# supply_switch.net
KiCad netlist of a schematic drawn in EAGLE
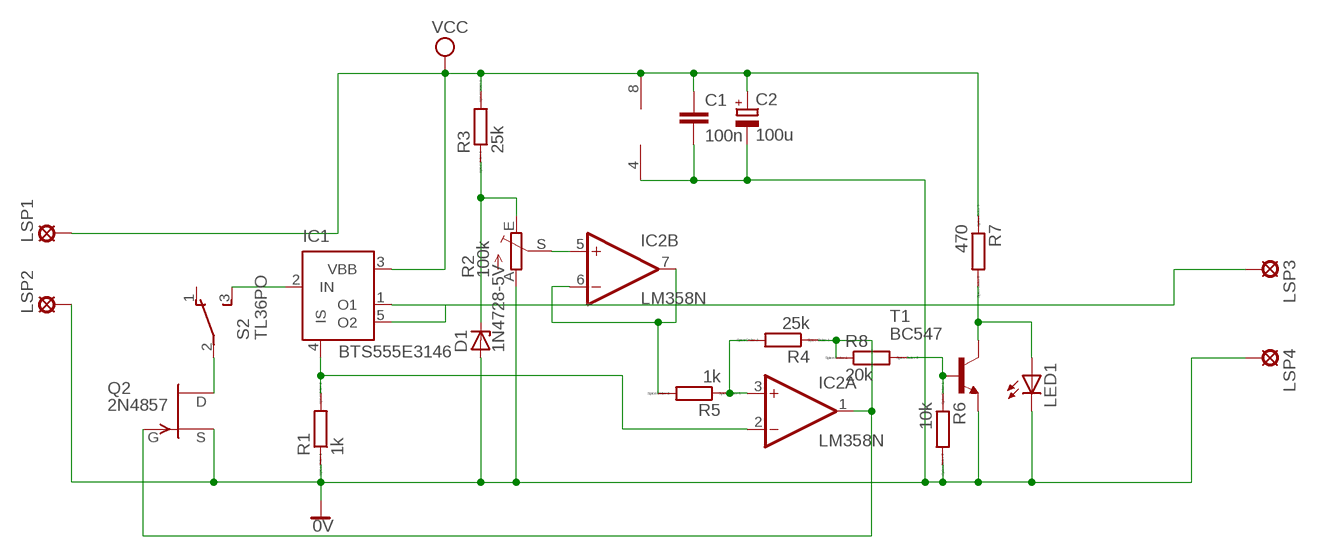
[diagram p0: schematic, sheet 1]

(export (version "E")
  (design (tool "Eeschema 10.0.6"))
  (components
    (comp (ref "C1")
      (value "100n")
      (footprint "eagle-import:C025-030X050")
      (libsource (lib "eagle-import") (part "C-EU025-030X050"))
    )
    (comp (ref "C2")
      (value "100u")
      (footprint "eagle-import:E3,5-10")
      (libsource (lib "eagle-import") (part "CPOL-EUE3.5-10"))
    )
    (comp (ref "D1")
      (value "1N4728-5V")
      (footprint "eagle-import:DO41Z10")
      (libsource (lib "eagle-import") (part "1N4728"))
    )
    (comp (ref "IC1")
      (value "BTS555E3146")
      (footprint "eagle-import:TO220-52")
      (libsource (lib "eagle-import") (part "BTS555E3146"))
    )
    (comp (ref "IC2")
      (value "LM358N")
      (footprint "eagle-import:DIL08")
      (libsource (lib "eagle-import") (part "LM358N"))
    )
    (comp (ref "LED1")
      (value "LED5MM")
      (footprint "eagle-import:LED5MM")
      (libsource (lib "eagle-import") (part "LED5MM"))
    )
    (comp (ref "LSP1")
      (value "SE14")
      (footprint "eagle-import:SE14")
      (libsource (lib "eagle-import") (part "SE14"))
    )
    (comp (ref "LSP2")
      (value "SE14")
      (footprint "eagle-import:SE14")
      (libsource (lib "eagle-import") (part "SE14"))
    )
    (comp (ref "LSP3")
      (value "SE14")
      (footprint "eagle-import:SE14")
      (libsource (lib "eagle-import") (part "SE14"))
    )
    (comp (ref "LSP4")
      (value "SE14")
      (footprint "eagle-import:SE14")
      (libsource (lib "eagle-import") (part "SE14"))
    )
    (comp (ref "Q2")
      (value "2N4857")
      (footprint "eagle-import:TO18")
      (libsource (lib "eagle-import") (part "2N4857"))
    )
    (comp (ref "R1")
      (value "1k")
      (footprint "eagle-import:0207_15")
      (libsource (lib "eagle-import") (part "R-EU_0207_15"))
    )
    (comp (ref "R2")
      (value "100k")
      (footprint "eagle-import:CA6H")
      (libsource (lib "eagle-import") (part "TRIM_EU-CA6H"))
    )
    (comp (ref "R3")
      (value "25k")
      (footprint "eagle-import:0207_15")
      (libsource (lib "eagle-import") (part "R-EU_0207_15"))
    )
    (comp (ref "R4")
      (value "25k")
      (footprint "eagle-import:0207_15")
      (libsource (lib "eagle-import") (part "R-EU_0207_15"))
    )
    (comp (ref "R5")
      (value "1k")
      (footprint "eagle-import:0207_15")
      (libsource (lib "eagle-import") (part "R-EU_0207_15"))
    )
    (comp (ref "R6")
      (value "10k")
      (footprint "eagle-import:0207_15")
      (libsource (lib "eagle-import") (part "R-EU_0207_15"))
    )
    (comp (ref "R7")
      (value "470")
      (footprint "eagle-import:0207_15")
      (libsource (lib "eagle-import") (part "R-EU_0207_15"))
    )
    (comp (ref "R8")
      (value "20k")
      (footprint "eagle-import:0207_15")
      (libsource (lib "eagle-import") (part "R-EU_0207_15"))
    )
    (comp (ref "S2")
      (value "TL36PO")
      (footprint "eagle-import:TL3XPO")
      (libsource (lib "eagle-import") (part "TL36PO"))
    )
    (comp (ref "T1")
      (value "BC547")
      (footprint "eagle-import:TO92")
      (libsource (lib "eagle-import") (part "BC547"))
    )
  )
  (nets
    (net (code "1") (name "0V") (class "Default")
      (node (ref "C1") (pin "2") (pinfunction "2_2") (pintype "passive"))
      (node (ref "C2") (pin "-") (pinfunction "-_-") (pintype "passive"))
      (node (ref "D1") (pin "A") (pinfunction "A_A") (pintype "passive"))
      (node (ref "IC2") (pin "4") (pinfunction "V-_4") (pintype "power_in"))
      (node (ref "LED1") (pin "K") (pinfunction "C_K") (pintype "passive"))
      (node (ref "LSP2") (pin "MP") (pinfunction "MP_MP") (pintype "passive"))
      (node (ref "LSP4") (pin "MP") (pinfunction "MP_MP") (pintype "passive"))
      (node (ref "Q2") (pin "1") (pinfunction "S_1") (pintype "passive"))
      (node (ref "R1") (pin "1") (pinfunction "1_1") (pintype "passive"))
      (node (ref "R2") (pin "A") (pinfunction "A_A") (pintype "passive"))
      (node (ref "R6") (pin "2") (pinfunction "2_2") (pintype "passive"))
      (node (ref "T1") (pin "1") (pinfunction "E_1") (pintype "passive"))
    )
    (net (code "2") (name "Net-(D1-PadC)") (class "Default")
      (node (ref "D1") (pin "C") (pinfunction "C_C") (pintype "passive"))
      (node (ref "R2") (pin "E") (pinfunction "E_E") (pintype "passive"))
      (node (ref "R3") (pin "1") (pinfunction "1_1") (pintype "passive"))
    )
    (net (code "3") (name "Net-(IC1-IN)") (class "Default")
      (node (ref "IC1") (pin "2") (pinfunction "IN_2") (pintype "input"))
      (node (ref "S2") (pin "3") (pinfunction "S_3") (pintype "passive"))
    )
    (net (code "4") (name "Net-(IC1-IS)") (class "Default")
      (node (ref "IC1") (pin "4") (pinfunction "IS_4") (pintype "passive"))
      (node (ref "IC2") (pin "2") (pinfunction "-IN_2") (pintype "input"))
      (node (ref "R1") (pin "2") (pinfunction "2_2") (pintype "passive"))
    )
    (net (code "5") (name "Net-(IC1-O1)") (class "Default")
      (node (ref "IC1") (pin "1") (pinfunction "O1_1") (pintype "passive"))
      (node (ref "IC1") (pin "5") (pinfunction "O2_5") (pintype "passive"))
      (node (ref "LSP3") (pin "MP") (pinfunction "MP_MP") (pintype "passive"))
    )
    (net (code "6") (name "Net-(IC2A-+IN)") (class "Default")
      (node (ref "IC2") (pin "3") (pinfunction "+IN_3") (pintype "input"))
      (node (ref "R4") (pin "2") (pinfunction "2_2") (pintype "passive"))
      (node (ref "R5") (pin "1") (pinfunction "1_1") (pintype "passive"))
    )
    (net (code "7") (name "Net-(IC2A-OUT)") (class "Default")
      (node (ref "IC2") (pin "1") (pinfunction "OUT_1") (pintype "output"))
      (node (ref "Q2") (pin "3") (pinfunction "G_3") (pintype "passive"))
      (node (ref "R4") (pin "1") (pinfunction "1_1") (pintype "passive"))
      (node (ref "R8") (pin "1") (pinfunction "1_1") (pintype "passive"))
    )
    (net (code "8") (name "Net-(IC2B-+IN)") (class "Default")
      (node (ref "IC2") (pin "5") (pinfunction "+IN_5") (pintype "input"))
      (node (ref "R2") (pin "S") (pinfunction "S_S") (pintype "passive"))
    )
    (net (code "9") (name "Net-(IC2B--IN)") (class "Default")
      (node (ref "IC2") (pin "6") (pinfunction "-IN_6") (pintype "input"))
      (node (ref "IC2") (pin "7") (pinfunction "OUT_7") (pintype "output"))
      (node (ref "R5") (pin "2") (pinfunction "2_2") (pintype "passive"))
    )
    (net (code "10") (name "Net-(Q2-D)") (class "Default")
      (node (ref "Q2") (pin "2") (pinfunction "D_2") (pintype "passive"))
      (node (ref "S2") (pin "2") (pinfunction "P_2") (pintype "passive"))
    )
    (net (code "11") (name "Net-(T1-B)") (class "Default")
      (node (ref "R6") (pin "1") (pinfunction "1_1") (pintype "passive"))
      (node (ref "R8") (pin "2") (pinfunction "2_2") (pintype "passive"))
      (node (ref "T1") (pin "2") (pinfunction "B_2") (pintype "passive"))
    )
    (net (code "12") (name "Net-(T1-C)") (class "Default")
      (node (ref "LED1") (pin "A") (pinfunction "A_A") (pintype "passive"))
      (node (ref "R7") (pin "2") (pinfunction "2_2") (pintype "passive"))
      (node (ref "T1") (pin "3") (pinfunction "C_3") (pintype "passive"))
    )
    (net (code "13") (name "VCC") (class "Default")
      (node (ref "C1") (pin "1") (pinfunction "1_1") (pintype "passive"))
      (node (ref "C2") (pin "+") (pinfunction "+_+") (pintype "passive"))
      (node (ref "IC1") (pin "3") (pinfunction "VBB_3") (pintype "passive"))
      (node (ref "IC2") (pin "8") (pinfunction "V+_8") (pintype "power_in"))
      (node (ref "LSP1") (pin "MP") (pinfunction "MP_MP") (pintype "passive"))
      (node (ref "R3") (pin "2") (pinfunction "2_2") (pintype "passive"))
      (node (ref "R7") (pin "1") (pinfunction "1_1") (pintype "passive"))
    )
    (net (code "14") (name "unconnected-(S2-O-Pad1)") (class "Default")
      (node (ref "S2") (pin "1") (pinfunction "O_1") (pintype "passive"))
    )
  )
)
